# RN4020_Breakout.net
KiCad netlist of a schematic drawn in EAGLE
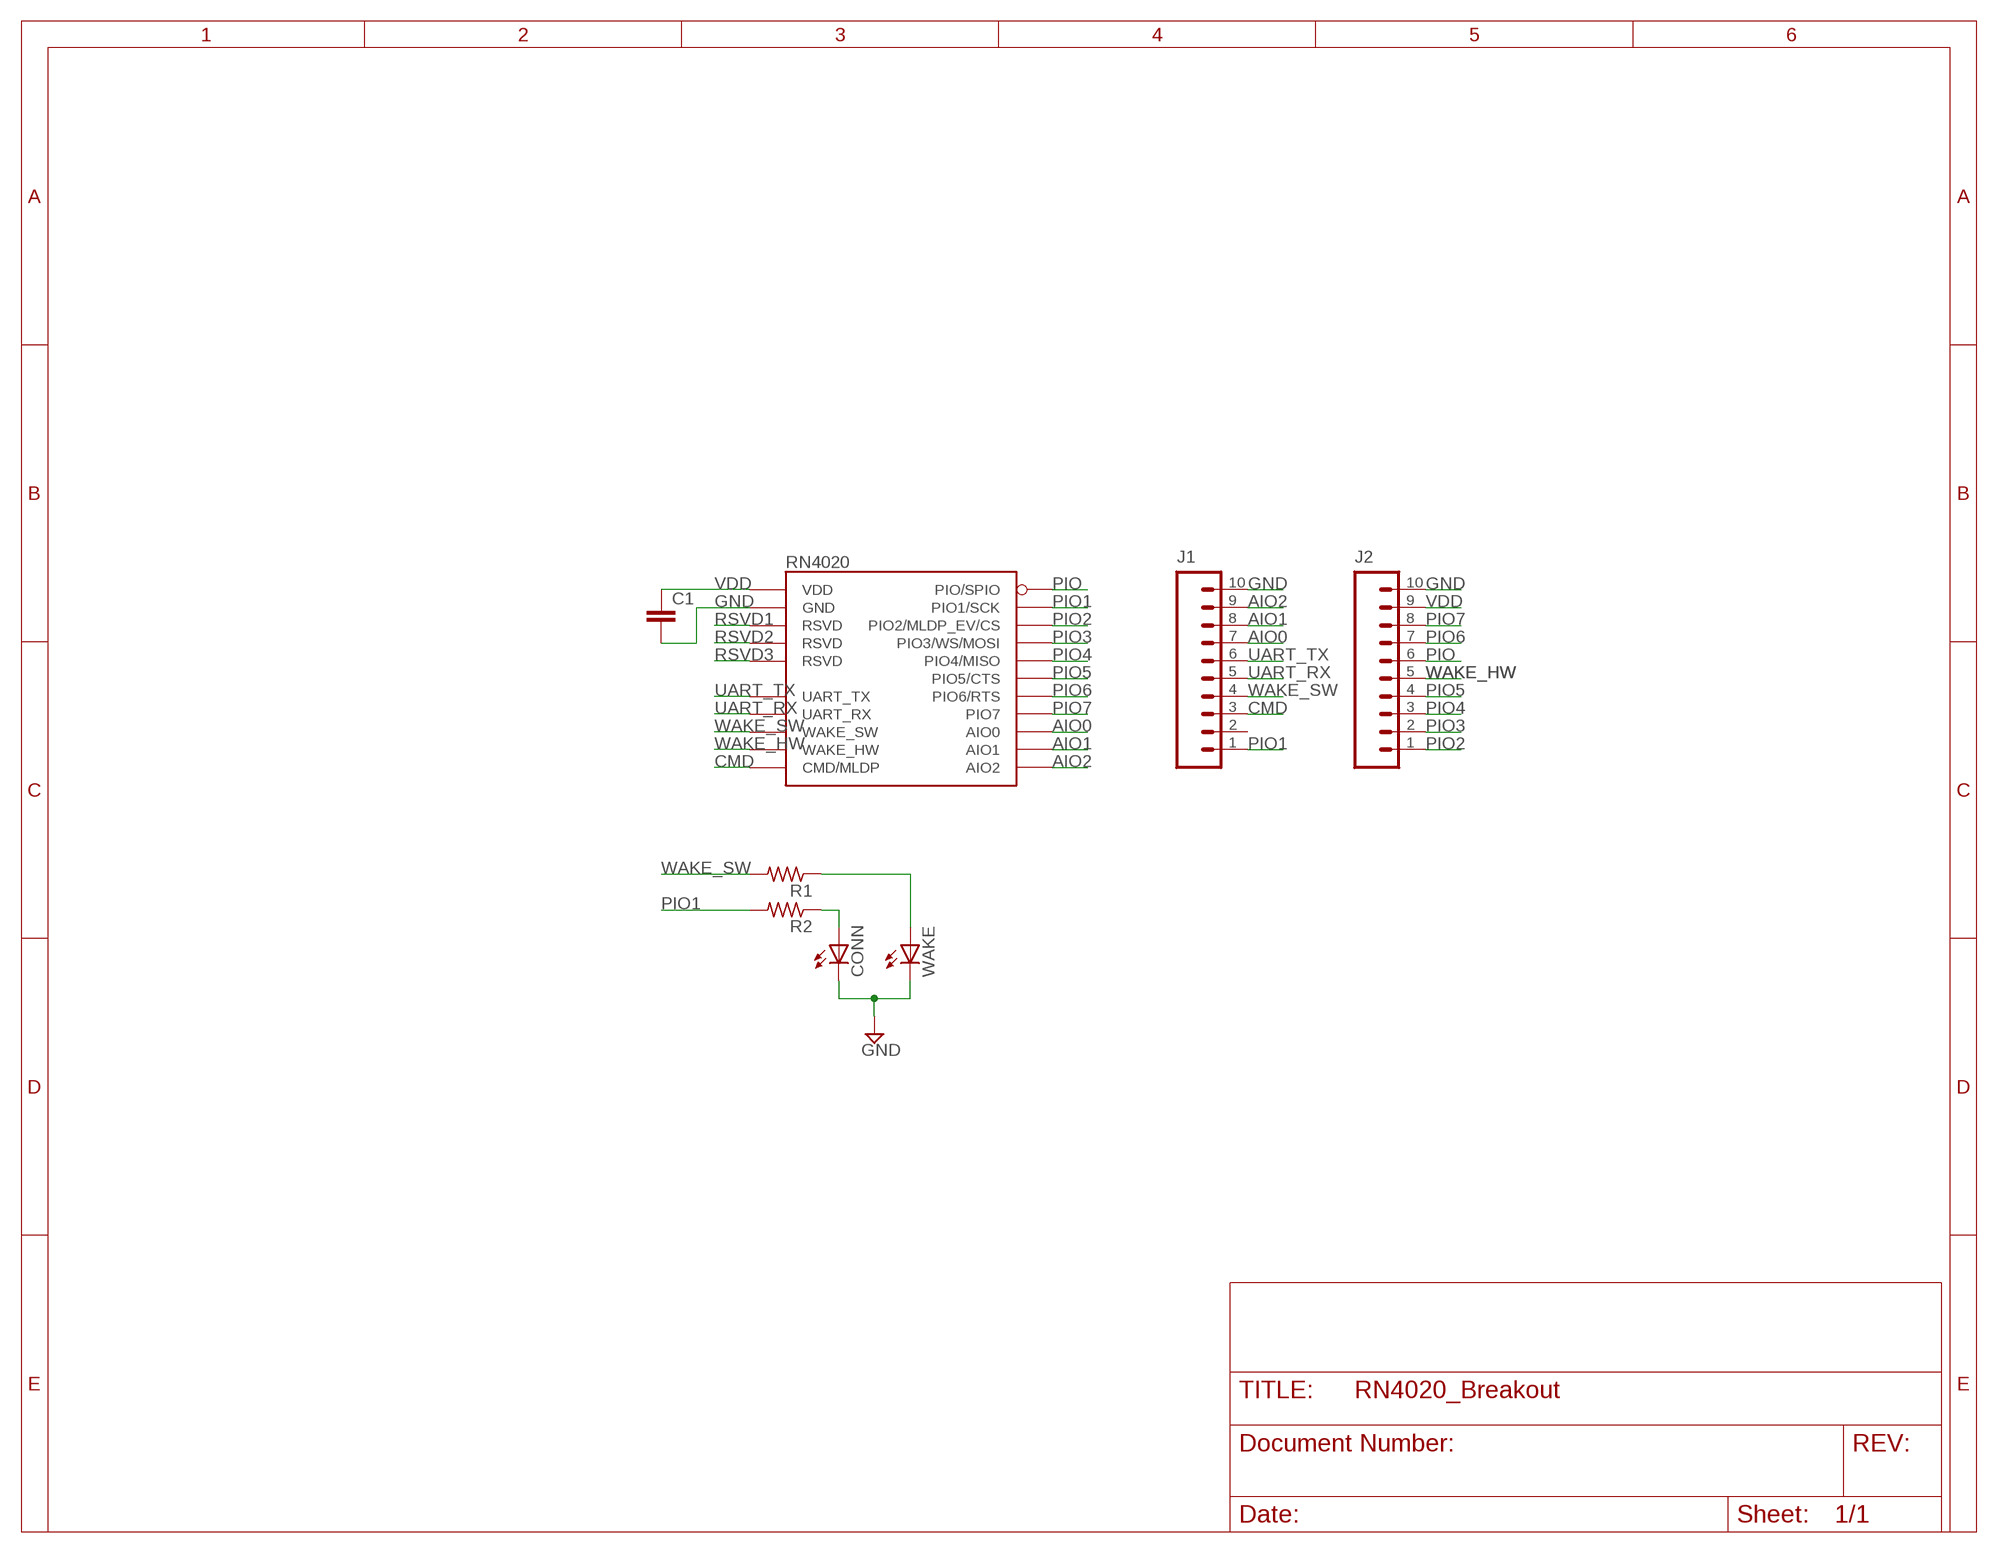
[diagram p0: schematic, sheet 1]

(export (version "E")
  (design (tool "Eeschema 10.0.6"))
  (components
    (comp (ref "C1")
      (value "C-EUC0805")
      (footprint "eagle-import:C0805")
      (libsource (lib "eagle-import") (part "C-EUC0805"))
    )
    (comp (ref "CONN")
      (value "LEDCHIPLED_0805")
      (footprint "eagle-import:CHIPLED_0805")
      (libsource (lib "eagle-import") (part "LEDCHIPLED_0805"))
    )
    (comp (ref "J1")
      (value "M10LOCK")
      (footprint "eagle-import:1X10_LOCK")
      (libsource (lib "eagle-import") (part "M10LOCK"))
    )
    (comp (ref "J2")
      (value "M10LOCK")
      (footprint "eagle-import:1X10_LOCK")
      (libsource (lib "eagle-import") (part "M10LOCK"))
    )
    (comp (ref "R1")
      (value "R-US_R0805")
      (footprint "eagle-import:R0805")
      (libsource (lib "eagle-import") (part "R-US_R0805"))
    )
    (comp (ref "R2")
      (value "R-US_R0805")
      (footprint "eagle-import:R0805")
      (libsource (lib "eagle-import") (part "R-US_R0805"))
    )
    (comp (ref "RN4020")
      (value "RN4020")
      (footprint "eagle-import:RN4020")
      (libsource (lib "eagle-import") (part "RN4020"))
    )
    (comp (ref "WAKE")
      (value "LEDCHIPLED_0805")
      (footprint "eagle-import:CHIPLED_0805")
      (libsource (lib "eagle-import") (part "LEDCHIPLED_0805"))
    )
  )
  (nets
    (net (code "1") (name "/AIO0") (class "Default")
      (node (ref "J1") (pin "7") (pinfunction "7_7") (pintype "passive"))
      (node (ref "RN4020") (pin "P$4") (pinfunction "AIO0_P$4") (pintype "bidirectional"))
    )
    (net (code "2") (name "/AIO1") (class "Default")
      (node (ref "J1") (pin "8") (pinfunction "8_8") (pintype "passive"))
      (node (ref "RN4020") (pin "P$3") (pinfunction "AIO1_P$3") (pintype "bidirectional"))
    )
    (net (code "3") (name "/AIO2") (class "Default")
      (node (ref "J1") (pin "9") (pinfunction "9_9") (pintype "passive"))
      (node (ref "RN4020") (pin "P$2") (pinfunction "AIO2_P$2") (pintype "bidirectional"))
    )
    (net (code "4") (name "/CMD") (class "Default")
      (node (ref "J1") (pin "3") (pinfunction "3_3") (pintype "passive"))
      (node (ref "RN4020") (pin "P$8") (pinfunction "CMD/MLDP_P$8") (pintype "bidirectional"))
    )
    (net (code "5") (name "/PIO") (class "Default")
      (node (ref "J2") (pin "6") (pinfunction "6_6") (pintype "passive"))
      (node (ref "RN4020") (pin "P$17") (pinfunction "PIO/SPIO_P$17") (pintype "bidirectional"))
    )
    (net (code "6") (name "/PIO1") (class "Default")
      (node (ref "J1") (pin "1") (pinfunction "1_1") (pintype "passive"))
      (node (ref "R2") (pin "2") (pinfunction "2_2") (pintype "passive"))
      (node (ref "RN4020") (pin "P$10") (pinfunction "PIO1/SCK_P$10") (pintype "bidirectional"))
    )
    (net (code "7") (name "/PIO2") (class "Default")
      (node (ref "J2") (pin "1") (pinfunction "1_1") (pintype "passive"))
      (node (ref "RN4020") (pin "P$11") (pinfunction "PIO2/MLDP_EV/CS_P$11") (pintype "bidirectional"))
    )
    (net (code "8") (name "/PIO3") (class "Default")
      (node (ref "J2") (pin "2") (pinfunction "2_2") (pintype "passive"))
      (node (ref "RN4020") (pin "P$12") (pinfunction "PIO3/WS/MOSI_P$12") (pintype "bidirectional"))
    )
    (net (code "9") (name "/PIO4") (class "Default")
      (node (ref "J2") (pin "3") (pinfunction "3_3") (pintype "passive"))
      (node (ref "RN4020") (pin "P$13") (pinfunction "PIO4/MISO_P$13") (pintype "bidirectional"))
    )
    (net (code "10") (name "/PIO5") (class "Default")
      (node (ref "J2") (pin "4") (pinfunction "4_4") (pintype "passive"))
      (node (ref "RN4020") (pin "P$14") (pinfunction "PIO5/CTS_P$14") (pintype "bidirectional"))
    )
    (net (code "11") (name "/PIO6") (class "Default")
      (node (ref "J2") (pin "7") (pinfunction "7_7") (pintype "passive"))
      (node (ref "RN4020") (pin "P$18") (pinfunction "PIO6/RTS_P$18") (pintype "bidirectional"))
    )
    (net (code "12") (name "/PIO7") (class "Default")
      (node (ref "J2") (pin "8") (pinfunction "8_8") (pintype "passive"))
      (node (ref "RN4020") (pin "P$19") (pinfunction "PIO7_P$19") (pintype "bidirectional"))
    )
    (net (code "13") (name "/RSVD1") (class "Default")
      (node (ref "RN4020") (pin "P$20") (pinfunction "RSVD_P$20") (pintype "bidirectional"))
    )
    (net (code "14") (name "/RSVD2") (class "Default")
      (node (ref "RN4020") (pin "P$21") (pinfunction "RSVD_P$21") (pintype "bidirectional"))
    )
    (net (code "15") (name "/RSVD3") (class "Default")
      (node (ref "RN4020") (pin "P$22") (pinfunction "RSVD_P$22") (pintype "bidirectional"))
    )
    (net (code "16") (name "/UART_RX") (class "Default")
      (node (ref "J1") (pin "5") (pinfunction "5_5") (pintype "passive"))
      (node (ref "RN4020") (pin "P$6") (pinfunction "UART_RX_P$6") (pintype "bidirectional"))
    )
    (net (code "17") (name "/UART_TX") (class "Default")
      (node (ref "J1") (pin "6") (pinfunction "6_6") (pintype "passive"))
      (node (ref "RN4020") (pin "P$5") (pinfunction "UART_TX_P$5") (pintype "bidirectional"))
    )
    (net (code "18") (name "/VDD") (class "Default")
      (node (ref "C1") (pin "1") (pinfunction "1_1") (pintype "passive"))
      (node (ref "J2") (pin "9") (pinfunction "9_9") (pintype "passive"))
      (node (ref "RN4020") (pin "P$23") (pinfunction "VDD_P$23") (pintype "bidirectional"))
    )
    (net (code "19") (name "/WAKE_HW") (class "Default")
      (node (ref "J2") (pin "5") (pinfunction "5_5") (pintype "passive"))
      (node (ref "RN4020") (pin "P$15") (pinfunction "WAKE_HW_P$15") (pintype "bidirectional"))
    )
    (net (code "20") (name "/WAKE_SW") (class "Default")
      (node (ref "J1") (pin "4") (pinfunction "4_4") (pintype "passive"))
      (node (ref "R1") (pin "2") (pinfunction "2_2") (pintype "passive"))
      (node (ref "RN4020") (pin "P$7") (pinfunction "WAKE_SW_P$7") (pintype "bidirectional"))
    )
    (net (code "21") (name "GND") (class "Default")
      (node (ref "C1") (pin "2") (pinfunction "2_2") (pintype "passive"))
      (node (ref "CONN") (pin "C") (pinfunction "C_C") (pintype "passive"))
      (node (ref "J1") (pin "10") (pinfunction "10_10") (pintype "passive"))
      (node (ref "J2") (pin "10") (pinfunction "10_10") (pintype "passive"))
      (node (ref "RN4020") (pin "P$1") (pinfunction "GND_P$1") (pintype "bidirectional"))
      (node (ref "RN4020") (pin "P$16") (pinfunction "GND_P$16") (pintype "bidirectional"))
      (node (ref "RN4020") (pin "P$24") (pinfunction "GND_P$24") (pintype "bidirectional"))
      (node (ref "RN4020") (pin "P$9") (pinfunction "GND_P$9") (pintype "bidirectional"))
      (node (ref "WAKE") (pin "C") (pinfunction "C_C") (pintype "passive"))
    )
    (net (code "22") (name "Net-(CONN-PadA)") (class "Default")
      (node (ref "CONN") (pin "A") (pinfunction "A_A") (pintype "passive"))
      (node (ref "R2") (pin "1") (pinfunction "1_1") (pintype "passive"))
    )
    (net (code "23") (name "Net-(R1-Pad1)") (class "Default")
      (node (ref "R1") (pin "1") (pinfunction "1_1") (pintype "passive"))
      (node (ref "WAKE") (pin "A") (pinfunction "A_A") (pintype "passive"))
    )
    (net (code "24") (name "unconnected-(J1-Pad2)") (class "Default")
      (node (ref "J1") (pin "2") (pinfunction "2_2") (pintype "passive"))
    )
  )
)
